# Jade_v1_schematics_PG4_AUX_PARTS.net
KiCad netlist of a schematic drawn in Altium Designer
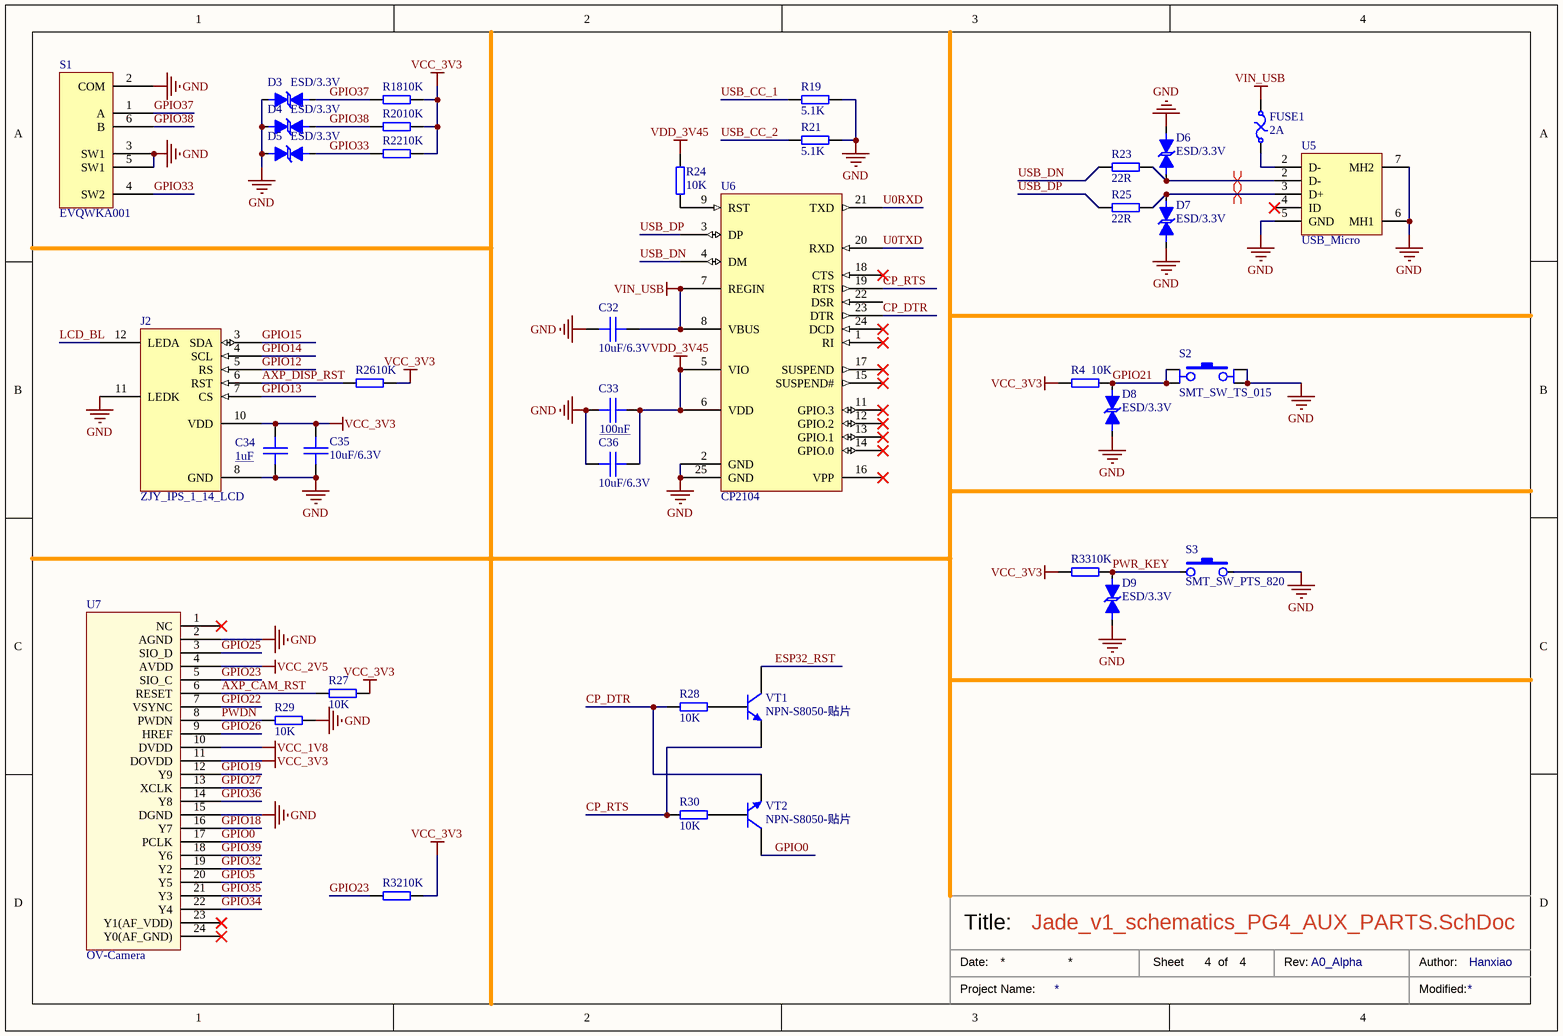
[diagram p0: Jade_v1_schematics_PG4_AUX_PARTS.SchDoc]

(export (version "E")
  (design (tool "Eeschema 10.0.6"))
  (components
    (comp (ref "C32")
      (value "10uF/6.3V")
      (footprint "SMT_C_0603")
      (description "Surface mount capacitor 0603")
      (libsource (lib "Vowstar_Basic_Device") (part "SMT_C_0603"))
    )
    (comp (ref "C33")
      (value "100nF")
      (footprint "SMT_C_0402")
      (description "Surface mount capacitor 0402")
      (libsource (lib "Vowstar_Basic_Device") (part "SMT_C_0402"))
    )
    (comp (ref "C34")
      (value "1uF")
      (footprint "SMT_C_0402")
      (description "Surface mount capacitor 0402")
      (libsource (lib "Vowstar_Basic_Device") (part "SMT_C_0402"))
    )
    (comp (ref "C35")
      (value "10uF/6.3V")
      (footprint "SMT_C_0603")
      (description "Surface mount capacitor 0603")
      (libsource (lib "Vowstar_Basic_Device") (part "SMT_C_0603"))
    )
    (comp (ref "C36")
      (value "10uF/6.3V")
      (footprint "SMT_C_0603")
      (description "Surface mount capacitor 0603")
      (libsource (lib "Vowstar_Basic_Device") (part "SMT_C_0603"))
    )
    (comp (ref "D3")
      (value "ESD/3.3V")
      (footprint "SMT_DIODE_SOD_523")
      (description "Surface mount bidirectional TVS diode SOD-523(0603) Package")
      (libsource (lib "Vowstar_Basic_Device") (part "SMT_DIODE_TVS_B_SOD_523"))
    )
    (comp (ref "D4")
      (value "ESD/3.3V")
      (footprint "SMT_DIODE_SOD_523")
      (description "Surface mount bidirectional TVS diode SOD-523(0603) Package")
      (libsource (lib "Vowstar_Basic_Device") (part "SMT_DIODE_TVS_B_SOD_523"))
    )
    (comp (ref "D5")
      (value "ESD/3.3V")
      (footprint "SMT_DIODE_SOD_523")
      (description "Surface mount bidirectional TVS diode SOD-523(0603) Package")
      (libsource (lib "Vowstar_Basic_Device") (part "SMT_DIODE_TVS_B_SOD_523"))
    )
    (comp (ref "D6")
      (value "ESD/3.3V")
      (footprint "SMT_DIODE_SOD_523")
      (description "Surface mount bidirectional TVS diode SOD-523(0603) Package")
      (libsource (lib "Vowstar_Basic_Device") (part "SMT_DIODE_TVS_B_SOD_523"))
    )
    (comp (ref "D7")
      (value "ESD/3.3V")
      (footprint "SMT_DIODE_SOD_523")
      (description "Surface mount bidirectional TVS diode SOD-523(0603) Package")
      (libsource (lib "Vowstar_Basic_Device") (part "SMT_DIODE_TVS_B_SOD_523"))
    )
    (comp (ref "D8")
      (value "ESD/3.3V")
      (footprint "SMT_DIODE_SOD_523")
      (description "Surface mount bidirectional TVS diode SOD-523(0603) Package")
      (libsource (lib "Vowstar_Basic_Device") (part "SMT_DIODE_TVS_B_SOD_523"))
    )
    (comp (ref "D9")
      (value "ESD/3.3V")
      (footprint "SMT_DIODE_SOD_523")
      (description "Surface mount bidirectional TVS diode SOD-523(0603) Package")
      (libsource (lib "Vowstar_Basic_Device") (part "SMT_DIODE_TVS_B_SOD_523"))
    )
    (comp (ref "FUSE1")
      (value "2A")
      (footprint "SMT_FUSE_0805")
      (description "SMT_FUSE_1812")
      (libsource (lib "Vowstar_Basic_Device") (part "SMT_FUSE_1812"))
    )
    (comp (ref "J2")
      (value "ZJY_IPS_1_14_LCD")
      (footprint "ZJY_1.3_HZ_13Pin")
      (libsource (lib "GENERAL-IC") (part "ZJY_IPS_1_14_LCD"))
    )
    (comp (ref "R4")
      (value "10K")
      (footprint "SMT_R_0402")
      (description "Surface mount resistor 0402")
      (libsource (lib "Vowstar_Basic_Device") (part "SMT_R_0402"))
    )
    (comp (ref "R18")
      (value "10K")
      (footprint "SMT_R_0402")
      (description "Surface mount resistor 0402")
      (libsource (lib "Vowstar_Basic_Device") (part "SMT_R_0402"))
    )
    (comp (ref "R19")
      (value "5.1K")
      (footprint "SMT_R_0402")
      (description "Surface mount resistor 0402")
      (libsource (lib "Vowstar_Basic_Device") (part "SMT_R_0402"))
    )
    (comp (ref "R20")
      (value "10K")
      (footprint "SMT_R_0402")
      (description "Surface mount resistor 0402")
      (libsource (lib "Vowstar_Basic_Device") (part "SMT_R_0402"))
    )
    (comp (ref "R21")
      (value "5.1K")
      (footprint "SMT_R_0402")
      (description "Surface mount resistor 0402")
      (libsource (lib "Vowstar_Basic_Device") (part "SMT_R_0402"))
    )
    (comp (ref "R22")
      (value "10K")
      (footprint "SMT_R_0402")
      (description "Surface mount resistor 0402")
      (libsource (lib "Vowstar_Basic_Device") (part "SMT_R_0402"))
    )
    (comp (ref "R23")
      (value "22R")
      (footprint "SMT_R_0402")
      (description "Surface mount resistor 0603")
      (libsource (lib "Vowstar_Basic_Device") (part "SMT_R_0603"))
    )
    (comp (ref "R24")
      (value "10K")
      (footprint "SMT_R_0402")
      (description "Surface mount resistor 0402")
      (libsource (lib "Vowstar_Basic_Device") (part "SMT_R_0402"))
    )
    (comp (ref "R25")
      (value "22R")
      (footprint "SMT_R_0402")
      (description "Surface mount resistor 0603")
      (libsource (lib "Vowstar_Basic_Device") (part "SMT_R_0603"))
    )
    (comp (ref "R26")
      (value "10K")
      (footprint "SMT_R_0402")
      (description "Surface mount resistor 0402")
      (libsource (lib "Vowstar_Basic_Device") (part "SMT_R_0402"))
    )
    (comp (ref "R27")
      (value "10K")
      (footprint "SMT_R_0402")
      (description "Surface mount resistor 0402")
      (libsource (lib "Vowstar_Basic_Device") (part "SMT_R_0402"))
    )
    (comp (ref "R28")
      (value "10K")
      (footprint "SMT_R_0402")
      (description "Surface mount resistor 0402")
      (libsource (lib "Vowstar_Basic_Device") (part "SMT_R_0402"))
    )
    (comp (ref "R29")
      (value "10K")
      (footprint "SMT_R_0402")
      (description "Surface mount resistor 0402")
      (libsource (lib "Vowstar_Basic_Device") (part "SMT_R_0402"))
    )
    (comp (ref "R30")
      (value "10K")
      (footprint "SMT_R_0402")
      (description "Surface mount resistor 0402")
      (libsource (lib "Vowstar_Basic_Device") (part "SMT_R_0402"))
    )
    (comp (ref "R32")
      (value "10K")
      (footprint "SMT_R_0402")
      (description "Surface mount resistor 0402")
      (libsource (lib "Vowstar_Basic_Device") (part "SMT_R_0402"))
    )
    (comp (ref "R33")
      (value "10K")
      (footprint "SMT_R_0402")
      (description "Surface mount resistor 0402")
      (libsource (lib "Vowstar_Basic_Device") (part "SMT_R_0402"))
    )
    (comp (ref "S1")
      (value "EVQWKA001")
      (footprint "EVQWKA001")
      (libsource (lib "GENERAL-IC") (part "EVQWKA001"))
    )
    (comp (ref "S2")
      (value "SMT_SW_TS_015")
      (footprint "SMT_SW_TS_015")
      (libsource (lib "Vowstar_Switch") (part "SMT_SW_TS_015"))
    )
    (comp (ref "S3")
      (value "SMT_SW_PTS_820")
      (footprint "SMT_SW_PTS_820")
      (description "SMT Tactile ‎Switch PTS 820 Series")
      (libsource (lib "Vowstar_Switch") (part "SMT_SW_PTS_820"))
    )
    (comp (ref "U5")
      (value "USB_Micro")
      (footprint "M5-USB-TC-2")
      (description "USB micro female")
      (libsource (lib "Vowstar_Connector") (part "USB_Micro"))
    )
    (comp (ref "U6")
      (value "CP2104")
      (footprint "QFN50P401X400X90_HS-25N")
      (description "单芯片USB转UART桥接器")
      (libsource (lib "USB-REL-CHUP") (part "CP2104"))
    )
    (comp (ref "U7")
      (value "OV-Camera")
      (footprint "FPC0.5-SMT-24P-B-DRAWER")
      (description "OV9650/OV2460/OV3640/OV5640")
      (libsource (lib "Vowstar_Module") (part "OV-Camera"))
    )
    (comp (ref "VT1")
      (value "NPN-S8050-贴片")
      (footprint "NPN-S8050-贴片")
      (libsource (lib "Vowstar_Basic_Device") (part "NPN-S8050-贴片"))
    )
    (comp (ref "VT2")
      (value "NPN-S8050-贴片")
      (footprint "NPN-S8050-贴片")
      (libsource (lib "Vowstar_Basic_Device") (part "NPN-S8050-贴片"))
    )
  )
  (nets
    (net (code "1") (name "/AXP_CAM_RST") (class "Default")
      (node (ref "R27") (pin "1") (pinfunction "1_1") (pintype "passive"))
      (node (ref "U7") (pin "6") (pinfunction "RESET_6") (pintype "passive"))
    )
    (net (code "2") (name "/AXP_DISP_RST") (class "Default")
      (node (ref "J2") (pin "6") (pinfunction "RST_6") (pintype "input"))
      (node (ref "R26") (pin "1") (pinfunction "1_1") (pintype "passive"))
    )
    (net (code "3") (name "/CP_DTR") (class "Default")
      (node (ref "R28") (pin "2") (pinfunction "2_2") (pintype "passive"))
      (node (ref "U6") (pin "23") (pinfunction "DTR_23") (pintype "output"))
      (node (ref "VT2") (pin "2") (pinfunction "E_2") (pintype "passive"))
    )
    (net (code "4") (name "/CP_RTS") (class "Default")
      (node (ref "R30") (pin "2") (pinfunction "2_2") (pintype "passive"))
      (node (ref "U6") (pin "19") (pinfunction "RTS_19") (pintype "output"))
      (node (ref "VT1") (pin "2") (pinfunction "E_2") (pintype "passive"))
    )
    (net (code "7") (name "/ESP32_RST") (class "Default")
      (node (ref "VT1") (pin "3") (pinfunction "C_3") (pintype "passive"))
    )
    (net (code "8") (name "/GPIO0") (class "Default")
      (node (ref "U7") (pin "17") (pinfunction "PCLK_17") (pintype "passive"))
      (node (ref "VT2") (pin "3") (pinfunction "C_3") (pintype "passive"))
    )
    (net (code "9") (name "/GPIO5") (class "Default")
      (node (ref "U7") (pin "20") (pinfunction "Y5_20") (pintype "passive"))
    )
    (net (code "10") (name "/GPIO12") (class "Default")
      (node (ref "J2") (pin "5") (pinfunction "RS_5") (pintype "input"))
    )
    (net (code "11") (name "/GPIO13") (class "Default")
      (node (ref "J2") (pin "7") (pinfunction "CS_7") (pintype "input"))
    )
    (net (code "12") (name "/GPIO14") (class "Default")
      (node (ref "J2") (pin "4") (pinfunction "SCL_4") (pintype "input"))
    )
    (net (code "13") (name "/GPIO15") (class "Default")
      (node (ref "J2") (pin "3") (pinfunction "SDA_3") (pintype "bidirectional"))
    )
    (net (code "14") (name "/GPIO18") (class "Default")
      (node (ref "U7") (pin "16") (pinfunction "Y7_16") (pintype "passive"))
    )
    (net (code "15") (name "/GPIO19") (class "Default")
      (node (ref "U7") (pin "12") (pinfunction "Y9_12") (pintype "passive"))
    )
    (net (code "16") (name "/GPIO21") (class "Default")
      (node (ref "D8") (pin "1") (pinfunction "A_1") (pintype "passive"))
      (node (ref "R4") (pin "2") (pinfunction "2_2") (pintype "passive"))
      (node (ref "S2") (pin "1") (pinfunction "PINA1_1") (pintype "passive"))
      (node (ref "S2") (pin "2") (pinfunction "PINA2_2") (pintype "passive"))
    )
    (net (code "17") (name "/GPIO22") (class "Default")
      (node (ref "U7") (pin "7") (pinfunction "VSYNC_7") (pintype "passive"))
    )
    (net (code "18") (name "/GPIO23") (class "Default")
      (node (ref "R32") (pin "1") (pinfunction "1_1") (pintype "passive"))
      (node (ref "U7") (pin "5") (pinfunction "SIO_C_5") (pintype "passive"))
    )
    (net (code "19") (name "/GPIO25") (class "Default")
      (node (ref "U7") (pin "3") (pinfunction "SIO_D_3") (pintype "passive"))
    )
    (net (code "20") (name "/GPIO26") (class "Default")
      (node (ref "U7") (pin "9") (pinfunction "HREF_9") (pintype "passive"))
    )
    (net (code "21") (name "/GPIO27") (class "Default")
      (node (ref "U7") (pin "13") (pinfunction "XCLK_13") (pintype "passive"))
    )
    (net (code "22") (name "/GPIO32") (class "Default")
      (node (ref "U7") (pin "19") (pinfunction "Y2_19") (pintype "passive"))
    )
    (net (code "23") (name "/GPIO33") (class "Default")
      (node (ref "D5") (pin "1") (pinfunction "A_1") (pintype "passive"))
      (node (ref "R22") (pin "1") (pinfunction "1_1") (pintype "passive"))
      (node (ref "S1") (pin "4") (pinfunction "SW2_4") (pintype "passive"))
    )
    (net (code "24") (name "/GPIO34") (class "Default")
      (node (ref "U7") (pin "22") (pinfunction "Y4_22") (pintype "passive"))
    )
    (net (code "25") (name "/GPIO35") (class "Default")
      (node (ref "U7") (pin "21") (pinfunction "Y3_21") (pintype "passive"))
    )
    (net (code "26") (name "/GPIO36") (class "Default")
      (node (ref "U7") (pin "14") (pinfunction "Y8_14") (pintype "passive"))
    )
    (net (code "27") (name "/GPIO37") (class "Default")
      (node (ref "D3") (pin "1") (pinfunction "A_1") (pintype "passive"))
      (node (ref "R18") (pin "1") (pinfunction "1_1") (pintype "passive"))
      (node (ref "S1") (pin "1") (pinfunction "A_1") (pintype "passive"))
    )
    (net (code "28") (name "/GPIO38") (class "Default")
      (node (ref "D4") (pin "1") (pinfunction "A_1") (pintype "passive"))
      (node (ref "R20") (pin "1") (pinfunction "1_1") (pintype "passive"))
      (node (ref "S1") (pin "6") (pinfunction "B_6") (pintype "passive"))
    )
    (net (code "29") (name "/GPIO39") (class "Default")
      (node (ref "U7") (pin "18") (pinfunction "Y6_18") (pintype "passive"))
    )
    (net (code "30") (name "/LCD_BL") (class "Default")
      (node (ref "J2") (pin "12") (pinfunction "LEDA_12") (pintype "passive"))
    )
    (net (code "31") (name "/PWDN") (class "Default")
      (node (ref "R29") (pin "1") (pinfunction "1_1") (pintype "passive"))
      (node (ref "U7") (pin "8") (pinfunction "PWDN_8") (pintype "passive"))
    )
    (net (code "32") (name "/PWR_KEY") (class "Default")
      (node (ref "D9") (pin "1") (pinfunction "A_1") (pintype "passive"))
      (node (ref "R33") (pin "2") (pinfunction "2_2") (pintype "passive"))
      (node (ref "S3") (pin "1") (pinfunction "1_1") (pintype "passive"))
    )
    (net (code "33") (name "/U0RXD") (class "Default")
      (node (ref "U6") (pin "21") (pinfunction "TXD_21") (pintype "output"))
    )
    (net (code "34") (name "/U0TXD") (class "Default")
      (node (ref "U6") (pin "20") (pinfunction "RXD_20") (pintype "input"))
    )
    (net (code "35") (name "/USB_CC_1") (class "Default")
      (node (ref "R19") (pin "2") (pinfunction "2_2") (pintype "passive"))
    )
    (net (code "36") (name "/USB_CC_2") (class "Default")
      (node (ref "R21") (pin "2") (pinfunction "2_2") (pintype "passive"))
    )
    (net (code "37") (name "/USB_DN") (class "Default")
      (node (ref "R23") (pin "2") (pinfunction "2_2") (pintype "passive"))
      (node (ref "U6") (pin "4") (pinfunction "DM_4") (pintype "bidirectional"))
    )
    (net (code "38") (name "/USB_DP") (class "Default")
      (node (ref "R25") (pin "2") (pinfunction "2_2") (pintype "passive"))
      (node (ref "U6") (pin "3") (pinfunction "DP_3") (pintype "bidirectional"))
    )
    (net (code "39") (name "GND") (class "Default")
      (node (ref "C32") (pin "1") (pinfunction "1_1") (pintype "passive"))
      (node (ref "C33") (pin "1") (pinfunction "1_1") (pintype "passive"))
      (node (ref "C34") (pin "1") (pinfunction "1_1") (pintype "passive"))
      (node (ref "C35") (pin "2") (pinfunction "2_2") (pintype "passive"))
      (node (ref "C36") (pin "1") (pinfunction "1_1") (pintype "passive"))
      (node (ref "D3") (pin "2") (pinfunction "K_2") (pintype "passive"))
      (node (ref "D4") (pin "2") (pinfunction "K_2") (pintype "passive"))
      (node (ref "D5") (pin "2") (pinfunction "K_2") (pintype "passive"))
      (node (ref "D6") (pin "1") (pinfunction "A_1") (pintype "passive"))
      (node (ref "D7") (pin "2") (pinfunction "K_2") (pintype "passive"))
      (node (ref "D8") (pin "2") (pinfunction "K_2") (pintype "passive"))
      (node (ref "D9") (pin "2") (pinfunction "K_2") (pintype "passive"))
      (node (ref "J2") (pin "11") (pinfunction "LEDK_11") (pintype "passive"))
      (node (ref "J2") (pin "8") (pinfunction "GND_8") (pintype "power_in"))
      (node (ref "R19") (pin "1") (pinfunction "1_1") (pintype "passive"))
      (node (ref "R21") (pin "1") (pinfunction "1_1") (pintype "passive"))
      (node (ref "R29") (pin "2") (pinfunction "2_2") (pintype "passive"))
      (node (ref "S1") (pin "2") (pinfunction "COM_2") (pintype "passive"))
      (node (ref "S1") (pin "3") (pinfunction "SW1_3") (pintype "passive"))
      (node (ref "S1") (pin "5") (pinfunction "SW1_5") (pintype "passive"))
      (node (ref "S2") (pin "3") (pinfunction "PINB1_3") (pintype "passive"))
      (node (ref "S2") (pin "4") (pinfunction "PINB2_4") (pintype "passive"))
      (node (ref "S3") (pin "2") (pinfunction "2_2") (pintype "passive"))
      (node (ref "U5") (pin "5") (pinfunction "GND_5") (pintype "passive"))
      (node (ref "U5") (pin "6") (pinfunction "MH1_6") (pintype "passive"))
      (node (ref "U5") (pin "7") (pinfunction "MH2_7") (pintype "passive"))
      (node (ref "U6") (pin "2") (pinfunction "GND_2") (pintype "power_in"))
      (node (ref "U6") (pin "25") (pinfunction "GND_25") (pintype "power_in"))
      (node (ref "U7") (pin "15") (pinfunction "DGND_15") (pintype "passive"))
      (node (ref "U7") (pin "2") (pinfunction "AGND_2") (pintype "passive"))
    )
    (net (code "40") (name "Net-(D6-K)") (class "Default")
      (node (ref "D6") (pin "2") (pinfunction "K_2") (pintype "passive"))
      (node (ref "R23") (pin "1") (pinfunction "1_1") (pintype "passive"))
      (node (ref "U5") (pin "2") (pinfunction "D-_2") (pintype "passive"))
    )
    (net (code "41") (name "Net-(D7-A)") (class "Default")
      (node (ref "D7") (pin "1") (pinfunction "A_1") (pintype "passive"))
      (node (ref "R25") (pin "1") (pinfunction "1_1") (pintype "passive"))
      (node (ref "U5") (pin "3") (pinfunction "D+_3") (pintype "passive"))
    )
    (net (code "42") (name "Net-(U5-D-)") (class "Default")
      (node (ref "FUSE1") (pin "1") (pinfunction "1_1") (pintype "passive"))
      (node (ref "U5") (pin "2") (pinfunction "D-_2") (pintype "passive"))
    )
    (net (code "43") (name "Net-(U6-RST)") (class "Default")
      (node (ref "R24") (pin "2") (pinfunction "2_2") (pintype "passive"))
      (node (ref "U6") (pin "9") (pinfunction "RST_9") (pintype "input"))
    )
    (net (code "44") (name "Net-(VT1-B)") (class "Default")
      (node (ref "R28") (pin "1") (pinfunction "1_1") (pintype "passive"))
      (node (ref "VT1") (pin "1") (pinfunction "B_1") (pintype "passive"))
    )
    (net (code "45") (name "Net-(VT2-B)") (class "Default")
      (node (ref "R30") (pin "1") (pinfunction "1_1") (pintype "passive"))
      (node (ref "VT2") (pin "1") (pinfunction "B_1") (pintype "passive"))
    )
    (net (code "46") (name "VCC_1V8") (class "Default")
      (node (ref "U7") (pin "10") (pinfunction "DVDD_10") (pintype "passive"))
    )
    (net (code "47") (name "VCC_2V5") (class "Default")
      (node (ref "U7") (pin "4") (pinfunction "AVDD_4") (pintype "passive"))
    )
    (net (code "48") (name "VCC_3V3") (class "Default")
      (node (ref "C34") (pin "2") (pinfunction "2_2") (pintype "passive"))
      (node (ref "C35") (pin "1") (pinfunction "1_1") (pintype "passive"))
      (node (ref "J2") (pin "10") (pinfunction "VDD_10") (pintype "power_in"))
      (node (ref "R18") (pin "2") (pinfunction "2_2") (pintype "passive"))
      (node (ref "R20") (pin "2") (pinfunction "2_2") (pintype "passive"))
      (node (ref "R22") (pin "2") (pinfunction "2_2") (pintype "passive"))
      (node (ref "R26") (pin "2") (pinfunction "2_2") (pintype "passive"))
      (node (ref "R27") (pin "2") (pinfunction "2_2") (pintype "passive"))
      (node (ref "R32") (pin "2") (pinfunction "2_2") (pintype "passive"))
      (node (ref "R33") (pin "1") (pinfunction "1_1") (pintype "passive"))
      (node (ref "R4") (pin "1") (pinfunction "1_1") (pintype "passive"))
      (node (ref "U7") (pin "11") (pinfunction "DOVDD_11") (pintype "passive"))
    )
    (net (code "49") (name "VDD_3V45") (class "Default")
      (node (ref "C33") (pin "2") (pinfunction "2_2") (pintype "passive"))
      (node (ref "C36") (pin "2") (pinfunction "2_2") (pintype "passive"))
      (node (ref "R24") (pin "1") (pinfunction "1_1") (pintype "passive"))
      (node (ref "U6") (pin "5") (pinfunction "VIO_5") (pintype "power_in"))
      (node (ref "U6") (pin "6") (pinfunction "VDD_6") (pintype "power_in"))
    )
    (net (code "50") (name "VIN_USB") (class "Default")
      (node (ref "C32") (pin "2") (pinfunction "2_2") (pintype "passive"))
      (node (ref "FUSE1") (pin "2") (pinfunction "2_2") (pintype "passive"))
      (node (ref "U6") (pin "7") (pinfunction "REGIN_7") (pintype "power_in"))
      (node (ref "U6") (pin "8") (pinfunction "VBUS_8") (pintype "power_in"))
    )
    (net (code "51") (name "unconnected-(U5-ID-Pad4)") (class "Default")
      (node (ref "U5") (pin "4") (pinfunction "ID_4") (pintype "passive+no_connect"))
    )
    (net (code "52") (name "unconnected-(U6-CTS-Pad18)") (class "Default")
      (node (ref "U6") (pin "18") (pinfunction "CTS_18") (pintype "input+no_connect"))
    )
    (net (code "53") (name "unconnected-(U6-DCD-Pad24)") (class "Default")
      (node (ref "U6") (pin "24") (pinfunction "DCD_24") (pintype "input+no_connect"))
    )
    (net (code "54") (name "unconnected-(U6-DSR-Pad22)") (class "Default")
      (node (ref "U6") (pin "22") (pinfunction "DSR_22") (pintype "input"))
    )
    (net (code "55") (name "unconnected-(U6-GPIO.0-Pad14)") (class "Default")
      (node (ref "U6") (pin "14") (pinfunction "GPIO.0_14") (pintype "bidirectional+no_connect"))
    )
    (net (code "56") (name "unconnected-(U6-GPIO.1-Pad13)") (class "Default")
      (node (ref "U6") (pin "13") (pinfunction "GPIO.1_13") (pintype "bidirectional+no_connect"))
    )
    (net (code "57") (name "unconnected-(U6-GPIO.2-Pad12)") (class "Default")
      (node (ref "U6") (pin "12") (pinfunction "GPIO.2_12") (pintype "bidirectional+no_connect"))
    )
    (net (code "58") (name "unconnected-(U6-GPIO.3-Pad11)") (class "Default")
      (node (ref "U6") (pin "11") (pinfunction "GPIO.3_11") (pintype "bidirectional+no_connect"))
    )
    (net (code "59") (name "unconnected-(U6-RI-Pad1)") (class "Default")
      (node (ref "U6") (pin "1") (pinfunction "RI_1") (pintype "input+no_connect"))
    )
    (net (code "60") (name "unconnected-(U6-SUSPEND#-Pad15)") (class "Default")
      (node (ref "U6") (pin "15") (pinfunction "SUSPEND#_15") (pintype "output+no_connect"))
    )
    (net (code "61") (name "unconnected-(U6-SUSPEND-Pad17)") (class "Default")
      (node (ref "U6") (pin "17") (pinfunction "SUSPEND_17") (pintype "output+no_connect"))
    )
    (net (code "62") (name "unconnected-(U6-VPP-Pad16)") (class "Default")
      (node (ref "U6") (pin "16") (pinfunction "VPP_16") (pintype "power_in+no_connect"))
    )
    (net (code "63") (name "unconnected-(U7-NC-Pad1)") (class "Default")
      (node (ref "U7") (pin "1") (pinfunction "NC_1") (pintype "passive+no_connect"))
    )
    (net (code "64") (name "unconnected-(U7-Y0(AF_GND)-Pad24)") (class "Default")
      (node (ref "U7") (pin "24") (pinfunction "Y0(AF_GND)_24") (pintype "passive+no_connect"))
    )
    (net (code "65") (name "unconnected-(U7-Y1(AF_VDD)-Pad23)") (class "Default")
      (node (ref "U7") (pin "23") (pinfunction "Y1(AF_VDD)_23") (pintype "passive+no_connect"))
    )
  )
)
